# Analog.net
KiCad netlist of a schematic drawn in Altium Designer
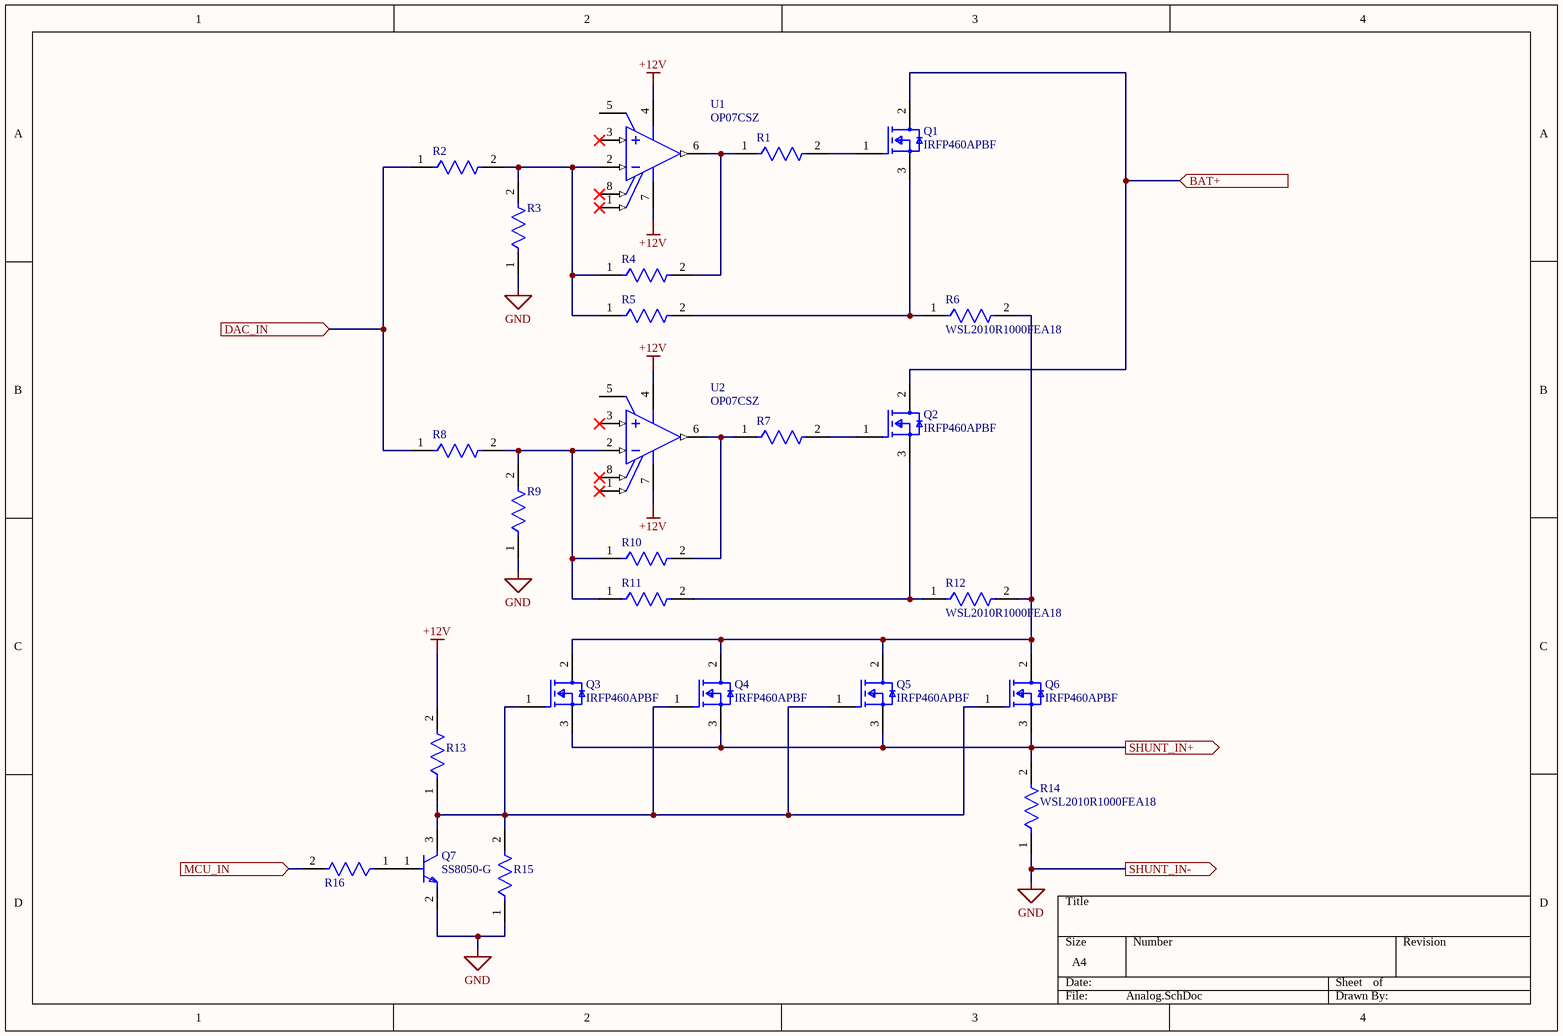
[diagram p0: Analog.SchDoc]

(export (version "E")
  (design (tool "Eeschema 10.0.6"))
  (components
    (comp (ref "Q1")
      (value "IRFP460APBF")
      (footprint "FP-X13-0103-MFG")
      (description "MOSFET N-CH 500V 20A TO-247AC")
      (fields
        (field (name "OCTOPART") "https://octopart.com/irfp460apbf-vishay-46526673")
        (field (name "MANUFACTURER") "Vishay")
      )
      (libsource (lib "Altium Content Vault") (part "277670f45256a45703965f138927d09"))
    )
    (comp (ref "Q2")
      (value "IRFP460APBF")
      (footprint "FP-X13-0103-MFG")
      (description "MOSFET N-CH 500V 20A TO-247AC")
      (fields
        (field (name "OCTOPART") "https://octopart.com/irfp460apbf-vishay-46526673")
        (field (name "MANUFACTURER") "Vishay")
      )
      (libsource (lib "Altium Content Vault") (part "277670f45256a45703965f138927d09"))
    )
    (comp (ref "Q3")
      (value "IRFP460APBF")
      (footprint "FP-X13-0103-MFG")
      (description "MOSFET N-CH 500V 20A TO-247AC")
      (fields
        (field (name "OCTOPART") "https://octopart.com/irfp460apbf-vishay-46526673")
        (field (name "MANUFACTURER") "Vishay")
      )
      (libsource (lib "Altium Content Vault") (part "277670f45256a45703965f138927d09"))
    )
    (comp (ref "Q4")
      (value "IRFP460APBF")
      (footprint "FP-X13-0103-MFG")
      (description "MOSFET N-CH 500V 20A TO-247AC")
      (fields
        (field (name "OCTOPART") "https://octopart.com/irfp460apbf-vishay-46526673")
        (field (name "MANUFACTURER") "Vishay")
      )
      (libsource (lib "Altium Content Vault") (part "277670f45256a45703965f138927d09"))
    )
    (comp (ref "Q5")
      (value "IRFP460APBF")
      (footprint "FP-X13-0103-MFG")
      (description "MOSFET N-CH 500V 20A TO-247AC")
      (fields
        (field (name "OCTOPART") "https://octopart.com/irfp460apbf-vishay-46526673")
        (field (name "MANUFACTURER") "Vishay")
      )
      (libsource (lib "Altium Content Vault") (part "277670f45256a45703965f138927d09"))
    )
    (comp (ref "Q6")
      (value "IRFP460APBF")
      (footprint "FP-X13-0103-MFG")
      (description "MOSFET N-CH 500V 20A TO-247AC")
      (fields
        (field (name "OCTOPART") "https://octopart.com/irfp460apbf-vishay-46526673")
        (field (name "MANUFACTURER") "Vishay")
      )
      (libsource (lib "Altium Content Vault") (part "277670f45256a45703965f138927d09"))
    )
    (comp (ref "Q7")
      (value "SS8050-G")
      (footprint "FP-SS8050-G-MFG")
      (description "NPN TRANSISTOR 1.5A 40V SOT-23 R")
      (libsource (lib "Altium Content Vault") (part "2a1388f82443b098dcd57d24ac7632d"))
    )
    (comp (ref "R1")
      (value "ERJ-P06F1002V")
      (footprint "FP-ERJP06-MFG")
      (description "RES SMD 10K OHM 1% 1/2W 0805")
      (fields (field (name "TOLERANCE") "1%"))
      (libsource (lib "Altium Content Vault") (part "1029c3af85768c4190bb7ad29bc67b5"))
    )
    (comp (ref "R2")
      (value "ERJ-P06F1002V")
      (footprint "FP-ERJP06-MFG")
      (description "RES SMD 10K OHM 1% 1/2W 0805")
      (fields (field (name "TOLERANCE") "1%"))
      (libsource (lib "Altium Content Vault") (part "1029c3af85768c4190bb7ad29bc67b5"))
    )
    (comp (ref "R3")
      (value "ERJ-P06F1002V")
      (footprint "FP-ERJP06-MFG")
      (description "RES SMD 10K OHM 1% 1/2W 0805")
      (fields (field (name "TOLERANCE") "1%"))
      (libsource (lib "Altium Content Vault") (part "1029c3af85768c4190bb7ad29bc67b5"))
    )
    (comp (ref "R4")
      (value "ERJ-P06F1002V")
      (footprint "FP-ERJP06-MFG")
      (description "RES SMD 10K OHM 1% 1/2W 0805")
      (fields (field (name "TOLERANCE") "1%"))
      (libsource (lib "Altium Content Vault") (part "1029c3af85768c4190bb7ad29bc67b5"))
    )
    (comp (ref "R5")
      (value "ERJ-P06F1002V")
      (footprint "FP-ERJP06-MFG")
      (description "RES SMD 10K OHM 1% 1/2W 0805")
      (fields (field (name "TOLERANCE") "1%"))
      (libsource (lib "Altium Content Vault") (part "1029c3af85768c4190bb7ad29bc67b5"))
    )
    (comp (ref "R6")
      (value "WSL2010R1000FEA18")
      (footprint "FP-WSL2010-0_508-IPC_A")
      (fields (field (name "TOLERANCE") "1%"))
      (libsource (lib "Altium Content Vault") (part "1029c3af85768c4190bb7ad29bc67b5"))
    )
    (comp (ref "R7")
      (value "ERJ-P06F1002V")
      (footprint "FP-ERJP06-MFG")
      (description "RES SMD 10K OHM 1% 1/2W 0805")
      (fields (field (name "TOLERANCE") "1%"))
      (libsource (lib "Altium Content Vault") (part "1029c3af85768c4190bb7ad29bc67b5"))
    )
    (comp (ref "R8")
      (value "ERJ-P06F1002V")
      (footprint "FP-ERJP06-MFG")
      (description "RES SMD 10K OHM 1% 1/2W 0805")
      (fields (field (name "TOLERANCE") "1%"))
      (libsource (lib "Altium Content Vault") (part "1029c3af85768c4190bb7ad29bc67b5"))
    )
    (comp (ref "R9")
      (value "ERJ-P06F1002V")
      (footprint "FP-ERJP06-MFG")
      (description "RES SMD 10K OHM 1% 1/2W 0805")
      (fields (field (name "TOLERANCE") "1%"))
      (libsource (lib "Altium Content Vault") (part "1029c3af85768c4190bb7ad29bc67b5"))
    )
    (comp (ref "R10")
      (value "ERJ-P06F1002V")
      (footprint "FP-ERJP06-MFG")
      (description "RES SMD 10K OHM 1% 1/2W 0805")
      (fields (field (name "TOLERANCE") "1%"))
      (libsource (lib "Altium Content Vault") (part "1029c3af85768c4190bb7ad29bc67b5"))
    )
    (comp (ref "R11")
      (value "ERJ-P06F1002V")
      (footprint "FP-ERJP06-MFG")
      (description "RES SMD 10K OHM 1% 1/2W 0805")
      (fields (field (name "TOLERANCE") "1%"))
      (libsource (lib "Altium Content Vault") (part "1029c3af85768c4190bb7ad29bc67b5"))
    )
    (comp (ref "R12")
      (value "WSL2010R1000FEA18")
      (footprint "FP-WSL2010-0_508-IPC_A")
      (fields (field (name "TOLERANCE") "1%"))
      (libsource (lib "Altium Content Vault") (part "1029c3af85768c4190bb7ad29bc67b5"))
    )
    (comp (ref "R13")
      (value "ERJ-P06F1002V")
      (footprint "FP-ERJP06-MFG")
      (description "RES SMD 10K OHM 1% 1/2W 0805")
      (fields (field (name "TOLERANCE") "1%"))
      (libsource (lib "Altium Content Vault") (part "1029c3af85768c4190bb7ad29bc67b5"))
    )
    (comp (ref "R14")
      (value "WSL2010R1000FEA18")
      (footprint "FP-WSL2010-0_508-IPC_A")
      (fields (field (name "TOLERANCE") "1%"))
      (libsource (lib "Altium Content Vault") (part "1029c3af85768c4190bb7ad29bc67b5"))
    )
    (comp (ref "R15")
      (value "ERJ-P06F1002V")
      (footprint "FP-ERJP06-MFG")
      (description "RES SMD 10K OHM 1% 1/2W 0805")
      (fields (field (name "TOLERANCE") "1%"))
      (libsource (lib "Altium Content Vault") (part "1029c3af85768c4190bb7ad29bc67b5"))
    )
    (comp (ref "R16")
      (value "ERJ-P06F1002V")
      (footprint "FP-ERJP06-MFG")
      (description "RES SMD 10K OHM 1% 1/2W 0805")
      (fields (field (name "TOLERANCE") "1%"))
      (libsource (lib "Altium Content Vault") (part "1029c3af85768c4190bb7ad29bc67b5"))
    )
    (comp (ref "U1")
      (value "OP07CSZ")
      (footprint "ADI-R-8_M")
      (fields (field (name "MANUFACTURER") "Analog Devices") (field (name "GENERIC PART NUMBER") "OP07"))
      (libsource (lib "Altium Content Vault") (part "ADI-OP07-R-8"))
    )
    (comp (ref "U2")
      (value "OP07CSZ")
      (footprint "ADI-R-8_M")
      (fields (field (name "MANUFACTURER") "Analog Devices") (field (name "GENERIC PART NUMBER") "OP07"))
      (libsource (lib "Altium Content Vault") (part "ADI-OP07-R-8"))
    )
  )
  (nets
    (net (code "1") (name "+12V") (class "Default")
      (node (ref "R13") (pin "2") (pinfunction "2_2") (pintype "passive"))
      (node (ref "U1") (pin "4") (pinfunction "-V_4") (pintype "power_in"))
      (node (ref "U1") (pin "7") (pinfunction "+V_7") (pintype "power_in"))
      (node (ref "U2") (pin "4") (pinfunction "-V_4") (pintype "power_in"))
      (node (ref "U2") (pin "7") (pinfunction "+V_7") (pintype "power_in"))
    )
    (net (code "2") (name "/BAT+") (class "Default")
      (node (ref "Q1") (pin "2") (pinfunction "D_2") (pintype "passive"))
      (node (ref "Q2") (pin "2") (pinfunction "D_2") (pintype "passive"))
    )
    (net (code "3") (name "/DAC_IN") (class "Default")
      (node (ref "R2") (pin "1") (pinfunction "1_1") (pintype "passive"))
      (node (ref "R8") (pin "1") (pinfunction "1_1") (pintype "passive"))
    )
    (net (code "4") (name "/MCU_IN") (class "Default")
      (node (ref "R16") (pin "2") (pinfunction "2_2") (pintype "passive"))
    )
    (net (code "5") (name "/SHUNT_IN+") (class "Default")
      (node (ref "Q3") (pin "3") (pinfunction "S_3") (pintype "passive"))
      (node (ref "Q4") (pin "3") (pinfunction "S_3") (pintype "passive"))
      (node (ref "Q5") (pin "3") (pinfunction "S_3") (pintype "passive"))
      (node (ref "Q6") (pin "3") (pinfunction "S_3") (pintype "passive"))
      (node (ref "R14") (pin "2") (pinfunction "2_2") (pintype "passive"))
    )
    (net (code "6") (name "GND") (class "Default")
      (node (ref "Q7") (pin "2") (pinfunction "E_2") (pintype "passive"))
      (node (ref "R14") (pin "1") (pinfunction "1_1") (pintype "passive"))
      (node (ref "R15") (pin "1") (pinfunction "1_1") (pintype "passive"))
      (node (ref "R3") (pin "1") (pinfunction "1_1") (pintype "passive"))
      (node (ref "R9") (pin "1") (pinfunction "1_1") (pintype "passive"))
    )
    (net (code "7") (name "Net-(Q1-G)") (class "Default")
      (node (ref "Q1") (pin "1") (pinfunction "G_1") (pintype "passive"))
      (node (ref "R1") (pin "2") (pinfunction "2_2") (pintype "passive"))
    )
    (net (code "8") (name "Net-(Q1-S)") (class "Default")
      (node (ref "Q1") (pin "3") (pinfunction "S_3") (pintype "passive"))
      (node (ref "R5") (pin "2") (pinfunction "2_2") (pintype "passive"))
      (node (ref "R6") (pin "1") (pinfunction "1_1") (pintype "passive"))
    )
    (net (code "9") (name "Net-(Q2-G)") (class "Default")
      (node (ref "Q2") (pin "1") (pinfunction "G_1") (pintype "passive"))
      (node (ref "R7") (pin "2") (pinfunction "2_2") (pintype "passive"))
    )
    (net (code "10") (name "Net-(Q2-S)") (class "Default")
      (node (ref "Q2") (pin "3") (pinfunction "S_3") (pintype "passive"))
      (node (ref "R11") (pin "2") (pinfunction "2_2") (pintype "passive"))
      (node (ref "R12") (pin "1") (pinfunction "1_1") (pintype "passive"))
    )
    (net (code "11") (name "Net-(Q3-D)") (class "Default")
      (node (ref "Q3") (pin "2") (pinfunction "D_2") (pintype "passive"))
      (node (ref "Q4") (pin "2") (pinfunction "D_2") (pintype "passive"))
      (node (ref "Q5") (pin "2") (pinfunction "D_2") (pintype "passive"))
      (node (ref "Q6") (pin "2") (pinfunction "D_2") (pintype "passive"))
      (node (ref "R12") (pin "2") (pinfunction "2_2") (pintype "passive"))
      (node (ref "R6") (pin "2") (pinfunction "2_2") (pintype "passive"))
    )
    (net (code "12") (name "Net-(Q3-G)") (class "Default")
      (node (ref "Q3") (pin "1") (pinfunction "G_1") (pintype "passive"))
      (node (ref "Q4") (pin "1") (pinfunction "G_1") (pintype "passive"))
      (node (ref "Q5") (pin "1") (pinfunction "G_1") (pintype "passive"))
      (node (ref "Q6") (pin "1") (pinfunction "G_1") (pintype "passive"))
      (node (ref "Q7") (pin "3") (pinfunction "C_3") (pintype "passive"))
      (node (ref "R13") (pin "1") (pinfunction "1_1") (pintype "passive"))
      (node (ref "R15") (pin "2") (pinfunction "2_2") (pintype "passive"))
    )
    (net (code "13") (name "Net-(Q7-B)") (class "Default")
      (node (ref "Q7") (pin "1") (pinfunction "B_1") (pintype "passive"))
      (node (ref "R16") (pin "1") (pinfunction "1_1") (pintype "passive"))
    )
    (net (code "14") (name "Net-(U1--IN)") (class "Default")
      (node (ref "R2") (pin "2") (pinfunction "2_2") (pintype "passive"))
      (node (ref "R3") (pin "2") (pinfunction "2_2") (pintype "passive"))
      (node (ref "R4") (pin "1") (pinfunction "1_1") (pintype "passive"))
      (node (ref "R5") (pin "1") (pinfunction "1_1") (pintype "passive"))
      (node (ref "U1") (pin "2") (pinfunction "-IN_2") (pintype "input"))
    )
    (net (code "15") (name "Net-(U1-OUT)") (class "Default")
      (node (ref "R1") (pin "1") (pinfunction "1_1") (pintype "passive"))
      (node (ref "R4") (pin "2") (pinfunction "2_2") (pintype "passive"))
      (node (ref "U1") (pin "6") (pinfunction "OUT_6") (pintype "output"))
    )
    (net (code "16") (name "Net-(U2--IN)") (class "Default")
      (node (ref "R10") (pin "1") (pinfunction "1_1") (pintype "passive"))
      (node (ref "R11") (pin "1") (pinfunction "1_1") (pintype "passive"))
      (node (ref "R8") (pin "2") (pinfunction "2_2") (pintype "passive"))
      (node (ref "R9") (pin "2") (pinfunction "2_2") (pintype "passive"))
      (node (ref "U2") (pin "2") (pinfunction "-IN_2") (pintype "input"))
    )
    (net (code "17") (name "Net-(U2-OUT)") (class "Default")
      (node (ref "R10") (pin "2") (pinfunction "2_2") (pintype "passive"))
      (node (ref "R7") (pin "1") (pinfunction "1_1") (pintype "passive"))
      (node (ref "U2") (pin "6") (pinfunction "OUT_6") (pintype "output"))
    )
    (net (code "18") (name "unconnected-(U1-+IN-Pad3)") (class "Default")
      (node (ref "U1") (pin "3") (pinfunction "+IN_3") (pintype "input+no_connect"))
    )
    (net (code "19") (name "unconnected-(U1-NC-Pad5)") (class "Default")
      (node (ref "U1") (pin "5") (pinfunction "NC_5") (pintype "passive"))
    )
    (net (code "20") (name "unconnected-(U1-VOS_TRIM-Pad1)") (class "Default")
      (node (ref "U1") (pin "1") (pinfunction "VOS_TRIM_1") (pintype "input+no_connect"))
    )
    (net (code "21") (name "unconnected-(U1-VOS_TRIM-Pad8)") (class "Default")
      (node (ref "U1") (pin "8") (pinfunction "VOS_TRIM_8") (pintype "input+no_connect"))
    )
    (net (code "22") (name "unconnected-(U2-+IN-Pad3)") (class "Default")
      (node (ref "U2") (pin "3") (pinfunction "+IN_3") (pintype "input+no_connect"))
    )
    (net (code "23") (name "unconnected-(U2-NC-Pad5)") (class "Default")
      (node (ref "U2") (pin "5") (pinfunction "NC_5") (pintype "passive"))
    )
    (net (code "24") (name "unconnected-(U2-VOS_TRIM-Pad1)") (class "Default")
      (node (ref "U2") (pin "1") (pinfunction "VOS_TRIM_1") (pintype "input+no_connect"))
    )
    (net (code "25") (name "unconnected-(U2-VOS_TRIM-Pad8)") (class "Default")
      (node (ref "U2") (pin "8") (pinfunction "VOS_TRIM_8") (pintype "input+no_connect"))
    )
  )
)
